# 1_FullBridge.net
KiCad netlist of a schematic drawn in Altium Designer
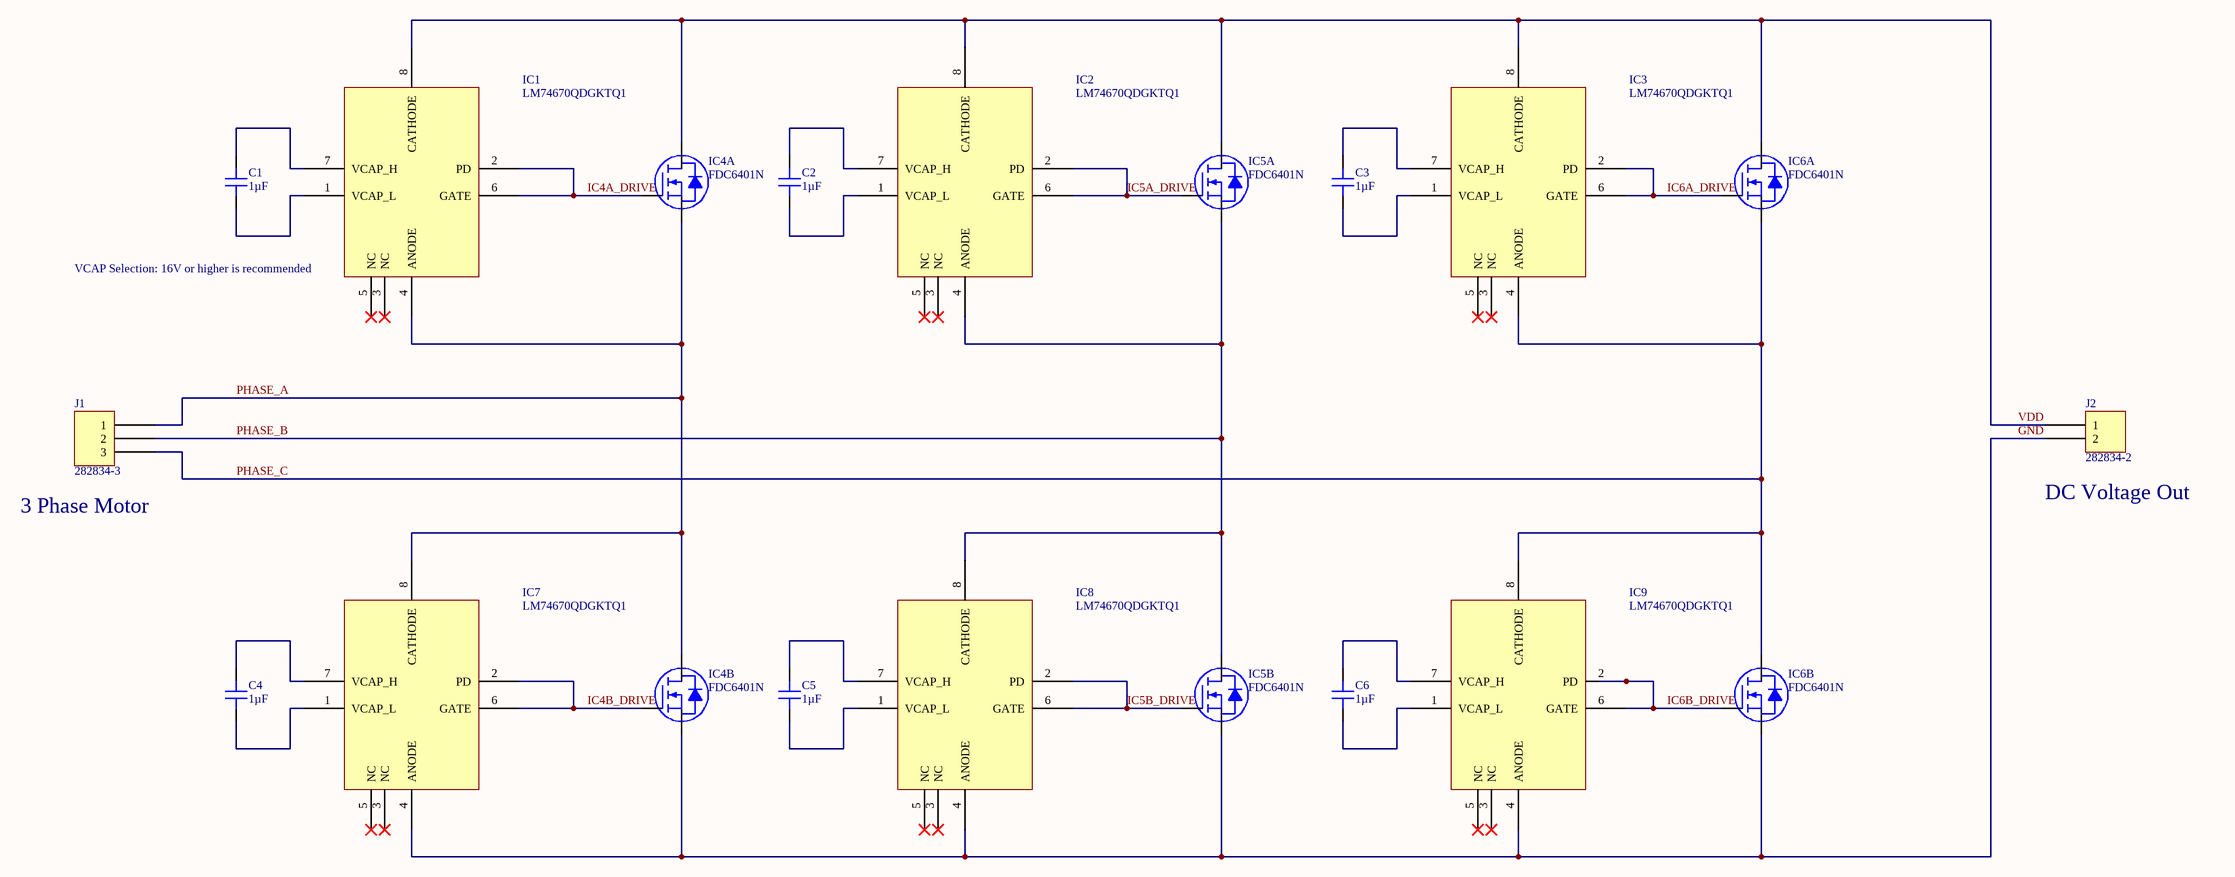
[diagram p0: 1_FullBridge.SchDoc]

(export (version "E")
  (design (tool "Eeschema 10.0.6"))
  (components
    (comp (ref "C1")
      (value "1µF")
      (footprint "CAP 0805_2012")
      (description "CAP CER 1UF 50V X7R 0805")
      (fields
        (field (name "PART NUMBER") "GCM21BR71H105KA03L")
        (field (name "MANUFACTURER") "Murata Electronics")
      )
      (libsource (lib "Celestial Altium Library - altium_library") (part "Capacitor"))
    )
    (comp (ref "C2")
      (value "1µF")
      (footprint "CAP 0805_2012")
      (description "CAP CER 1UF 50V X7R 0805")
      (fields
        (field (name "PART NUMBER") "GCM21BR71H105KA03L")
        (field (name "MANUFACTURER") "Murata Electronics")
      )
      (libsource (lib "Celestial Altium Library - altium_library") (part "Capacitor"))
    )
    (comp (ref "C3")
      (value "1µF")
      (footprint "CAP 0805_2012")
      (description "CAP CER 1UF 50V X7R 0805")
      (fields
        (field (name "PART NUMBER") "GCM21BR71H105KA03L")
        (field (name "MANUFACTURER") "Murata Electronics")
      )
      (libsource (lib "Celestial Altium Library - altium_library") (part "Capacitor"))
    )
    (comp (ref "C4")
      (value "1µF")
      (footprint "CAP 0805_2012")
      (description "CAP CER 1UF 50V X7R 0805")
      (fields
        (field (name "PART NUMBER") "GCM21BR71H105KA03L")
        (field (name "MANUFACTURER") "Murata Electronics")
      )
      (libsource (lib "Celestial Altium Library - altium_library") (part "Capacitor"))
    )
    (comp (ref "C5")
      (value "1µF")
      (footprint "CAP 0805_2012")
      (description "CAP CER 1UF 50V X7R 0805")
      (fields
        (field (name "PART NUMBER") "GCM21BR71H105KA03L")
        (field (name "MANUFACTURER") "Murata Electronics")
      )
      (libsource (lib "Celestial Altium Library - altium_library") (part "Capacitor"))
    )
    (comp (ref "C6")
      (value "1µF")
      (footprint "CAP 0805_2012")
      (description "CAP CER 1UF 50V X7R 0805")
      (fields
        (field (name "PART NUMBER") "GCM21BR71H105KA03L")
        (field (name "MANUFACTURER") "Murata Electronics")
      )
      (libsource (lib "Celestial Altium Library - altium_library") (part "Capacitor"))
    )
    (comp (ref "IC1")
      (value "LM74670QDGKTQ1")
      (footprint "TI_8VSSOP")
      (description "Zero IQ Smart Diode Rectifier Controller")
      (libsource (lib "bb_kinetic_harvester") (part "TI LM74670-Q1"))
    )
    (comp (ref "IC2")
      (value "LM74670QDGKTQ1")
      (footprint "TI_8VSSOP")
      (description "Zero IQ Smart Diode Rectifier Controller")
      (libsource (lib "bb_kinetic_harvester") (part "TI LM74670-Q1"))
    )
    (comp (ref "IC3")
      (value "LM74670QDGKTQ1")
      (footprint "TI_8VSSOP")
      (description "Zero IQ Smart Diode Rectifier Controller")
      (libsource (lib "bb_kinetic_harvester") (part "TI LM74670-Q1"))
    )
    (comp (ref "IC4")
      (value "FDC6401N")
      (footprint "FAIRCHILD SOT-23-6 SUPERSOT-6")
      (description "MOSFET 2N-CH 20V 3A SSOT-6")
      (fields (field (name "MANUFACTURER") "ON Semiconductor"))
      (libsource (lib "Celestial Altium Library - altium_library") (part "FAIRCHILD DUAL MOSFET N-CH SOT-23-6"))
    )
    (comp (ref "IC5")
      (value "FDC6401N")
      (footprint "FAIRCHILD SOT-23-6 SUPERSOT-6")
      (description "MOSFET 2N-CH 20V 3A SSOT-6")
      (fields (field (name "MANUFACTURER") "ON Semiconductor"))
      (libsource (lib "Celestial Altium Library - altium_library") (part "FAIRCHILD DUAL MOSFET N-CH SOT-23-6"))
    )
    (comp (ref "IC6")
      (value "FDC6401N")
      (footprint "FAIRCHILD SOT-23-6 SUPERSOT-6")
      (description "MOSFET 2N-CH 20V 3A SSOT-6")
      (fields (field (name "MANUFACTURER") "ON Semiconductor"))
      (libsource (lib "Celestial Altium Library - altium_library") (part "FAIRCHILD DUAL MOSFET N-CH SOT-23-6"))
    )
    (comp (ref "IC7")
      (value "LM74670QDGKTQ1")
      (footprint "TI_8VSSOP")
      (description "Zero IQ Smart Diode Rectifier Controller")
      (libsource (lib "bb_kinetic_harvester") (part "TI LM74670-Q1"))
    )
    (comp (ref "IC8")
      (value "LM74670QDGKTQ1")
      (footprint "TI_8VSSOP")
      (description "Zero IQ Smart Diode Rectifier Controller")
      (libsource (lib "bb_kinetic_harvester") (part "TI LM74670-Q1"))
    )
    (comp (ref "IC9")
      (value "LM74670QDGKTQ1")
      (footprint "TI_8VSSOP")
      (description "Zero IQ Smart Diode Rectifier Controller")
      (libsource (lib "bb_kinetic_harvester") (part "TI LM74670-Q1"))
    )
    (comp (ref "J1")
      (value "282834-3")
      (footprint "TE 282834-3")
      (description "TERM BLK 3P SIDE ENT 2.54MM PCB")
      (fields (field (name "MANUFACTURER") "TE Connectivity AMP Connectors") (field (name "VOLTAGE") "150V"))
      (libsource (lib "Celestial Altium Library - altium_library") (part "3 Pin"))
    )
    (comp (ref "J2")
      (value "282834-2")
      (footprint "TE 282834-2")
      (description "TERM BLK 2P SIDE ENT 2.54MM PCB")
      (fields (field (name "MANUFACTURER") "TE Connectivity AMP Connectors") (field (name "VOLTAGE") "150V"))
      (libsource (lib "Celestial Altium Library - altium_library") (part "2 Pin"))
    )
  )
  (nets
    (net (code "1") (name "/GND") (class "Default")
      (node (ref "IC4") (pin "2") (pinfunction "S2_2") (pintype "passive"))
      (node (ref "IC5") (pin "2") (pinfunction "S2_2") (pintype "passive"))
      (node (ref "IC6") (pin "2") (pinfunction "S2_2") (pintype "passive"))
      (node (ref "IC7") (pin "4") (pinfunction "ANODE_4") (pintype "passive"))
      (node (ref "IC8") (pin "4") (pinfunction "ANODE_4") (pintype "passive"))
      (node (ref "IC9") (pin "4") (pinfunction "ANODE_4") (pintype "passive"))
      (node (ref "J2") (pin "2") (pinfunction "2_2") (pintype "passive"))
    )
    (net (code "2") (name "/IC4A_DRIVE") (class "Default")
      (node (ref "IC1") (pin "2") (pinfunction "PD_2") (pintype "passive"))
      (node (ref "IC1") (pin "6") (pinfunction "GATE_6") (pintype "passive"))
      (node (ref "IC4") (pin "1") (pinfunction "G1_1") (pintype "passive"))
    )
    (net (code "3") (name "/IC4B_DRIVE") (class "Default")
      (node (ref "IC4") (pin "3") (pinfunction "G2_3") (pintype "passive"))
      (node (ref "IC7") (pin "2") (pinfunction "PD_2") (pintype "passive"))
      (node (ref "IC7") (pin "6") (pinfunction "GATE_6") (pintype "passive"))
    )
    (net (code "4") (name "/IC5A_DRIVE") (class "Default")
      (node (ref "IC2") (pin "2") (pinfunction "PD_2") (pintype "passive"))
      (node (ref "IC2") (pin "6") (pinfunction "GATE_6") (pintype "passive"))
      (node (ref "IC5") (pin "1") (pinfunction "G1_1") (pintype "passive"))
    )
    (net (code "5") (name "/IC5B_DRIVE") (class "Default")
      (node (ref "IC5") (pin "3") (pinfunction "G2_3") (pintype "passive"))
      (node (ref "IC8") (pin "2") (pinfunction "PD_2") (pintype "passive"))
      (node (ref "IC8") (pin "6") (pinfunction "GATE_6") (pintype "passive"))
    )
    (net (code "6") (name "/IC6A_DRIVE") (class "Default")
      (node (ref "IC3") (pin "2") (pinfunction "PD_2") (pintype "passive"))
      (node (ref "IC3") (pin "6") (pinfunction "GATE_6") (pintype "passive"))
      (node (ref "IC6") (pin "1") (pinfunction "G1_1") (pintype "passive"))
    )
    (net (code "7") (name "/IC6B_DRIVE") (class "Default")
      (node (ref "IC6") (pin "3") (pinfunction "G2_3") (pintype "passive"))
      (node (ref "IC9") (pin "2") (pinfunction "PD_2") (pintype "passive"))
      (node (ref "IC9") (pin "6") (pinfunction "GATE_6") (pintype "passive"))
    )
    (net (code "8") (name "/PHASE_A") (class "Default")
      (node (ref "IC1") (pin "4") (pinfunction "ANODE_4") (pintype "passive"))
      (node (ref "IC4") (pin "4") (pinfunction "D2_4") (pintype "passive"))
      (node (ref "IC4") (pin "5") (pinfunction "S1_5") (pintype "passive"))
      (node (ref "IC7") (pin "8") (pinfunction "CATHODE_8") (pintype "passive"))
      (node (ref "J1") (pin "1") (pinfunction "1_1") (pintype "passive"))
    )
    (net (code "9") (name "/PHASE_B") (class "Default")
      (node (ref "IC2") (pin "4") (pinfunction "ANODE_4") (pintype "passive"))
      (node (ref "IC5") (pin "4") (pinfunction "D2_4") (pintype "passive"))
      (node (ref "IC5") (pin "5") (pinfunction "S1_5") (pintype "passive"))
      (node (ref "IC8") (pin "8") (pinfunction "CATHODE_8") (pintype "passive"))
      (node (ref "J1") (pin "2") (pinfunction "2_2") (pintype "passive"))
    )
    (net (code "10") (name "/PHASE_C") (class "Default")
      (node (ref "IC3") (pin "4") (pinfunction "ANODE_4") (pintype "passive"))
      (node (ref "IC6") (pin "4") (pinfunction "D2_4") (pintype "passive"))
      (node (ref "IC6") (pin "5") (pinfunction "S1_5") (pintype "passive"))
      (node (ref "IC9") (pin "8") (pinfunction "CATHODE_8") (pintype "passive"))
      (node (ref "J1") (pin "3") (pinfunction "3_3") (pintype "passive"))
    )
    (net (code "11") (name "/VDD") (class "Default")
      (node (ref "IC1") (pin "8") (pinfunction "CATHODE_8") (pintype "passive"))
      (node (ref "IC2") (pin "8") (pinfunction "CATHODE_8") (pintype "passive"))
      (node (ref "IC3") (pin "8") (pinfunction "CATHODE_8") (pintype "passive"))
      (node (ref "IC4") (pin "6") (pinfunction "D1_6") (pintype "passive"))
      (node (ref "IC5") (pin "6") (pinfunction "D1_6") (pintype "passive"))
      (node (ref "IC6") (pin "6") (pinfunction "D1_6") (pintype "passive"))
      (node (ref "J2") (pin "1") (pinfunction "1_1") (pintype "passive"))
    )
    (net (code "12") (name "Net-(IC1-VCAP_H)") (class "Default")
      (node (ref "C1") (pin "1") (pinfunction "1_1") (pintype "passive"))
      (node (ref "IC1") (pin "7") (pinfunction "VCAP_H_7") (pintype "passive"))
    )
    (net (code "13") (name "Net-(IC1-VCAP_L)") (class "Default")
      (node (ref "C1") (pin "2") (pinfunction "2_2") (pintype "passive"))
      (node (ref "IC1") (pin "1") (pinfunction "VCAP_L_1") (pintype "passive"))
    )
    (net (code "14") (name "Net-(IC2-VCAP_H)") (class "Default")
      (node (ref "C2") (pin "1") (pinfunction "1_1") (pintype "passive"))
      (node (ref "IC2") (pin "7") (pinfunction "VCAP_H_7") (pintype "passive"))
    )
    (net (code "15") (name "Net-(IC2-VCAP_L)") (class "Default")
      (node (ref "C2") (pin "2") (pinfunction "2_2") (pintype "passive"))
      (node (ref "IC2") (pin "1") (pinfunction "VCAP_L_1") (pintype "passive"))
    )
    (net (code "16") (name "Net-(IC3-VCAP_H)") (class "Default")
      (node (ref "C3") (pin "1") (pinfunction "1_1") (pintype "passive"))
      (node (ref "IC3") (pin "7") (pinfunction "VCAP_H_7") (pintype "passive"))
    )
    (net (code "17") (name "Net-(IC3-VCAP_L)") (class "Default")
      (node (ref "C3") (pin "2") (pinfunction "2_2") (pintype "passive"))
      (node (ref "IC3") (pin "1") (pinfunction "VCAP_L_1") (pintype "passive"))
    )
    (net (code "18") (name "Net-(IC7-VCAP_H)") (class "Default")
      (node (ref "C4") (pin "1") (pinfunction "1_1") (pintype "passive"))
      (node (ref "IC7") (pin "7") (pinfunction "VCAP_H_7") (pintype "passive"))
    )
    (net (code "19") (name "Net-(IC7-VCAP_L)") (class "Default")
      (node (ref "C4") (pin "2") (pinfunction "2_2") (pintype "passive"))
      (node (ref "IC7") (pin "1") (pinfunction "VCAP_L_1") (pintype "passive"))
    )
    (net (code "20") (name "Net-(IC8-VCAP_H)") (class "Default")
      (node (ref "C5") (pin "1") (pinfunction "1_1") (pintype "passive"))
      (node (ref "IC8") (pin "7") (pinfunction "VCAP_H_7") (pintype "passive"))
    )
    (net (code "21") (name "Net-(IC8-VCAP_L)") (class "Default")
      (node (ref "C5") (pin "2") (pinfunction "2_2") (pintype "passive"))
      (node (ref "IC8") (pin "1") (pinfunction "VCAP_L_1") (pintype "passive"))
    )
    (net (code "22") (name "Net-(IC9-VCAP_H)") (class "Default")
      (node (ref "C6") (pin "1") (pinfunction "1_1") (pintype "passive"))
      (node (ref "IC9") (pin "7") (pinfunction "VCAP_H_7") (pintype "passive"))
    )
    (net (code "23") (name "Net-(IC9-VCAP_L)") (class "Default")
      (node (ref "C6") (pin "2") (pinfunction "2_2") (pintype "passive"))
      (node (ref "IC9") (pin "1") (pinfunction "VCAP_L_1") (pintype "passive"))
    )
    (net (code "24") (name "unconnected-(IC1-NC-Pad3)") (class "Default")
      (node (ref "IC1") (pin "3") (pinfunction "NC_3") (pintype "passive+no_connect"))
    )
    (net (code "25") (name "unconnected-(IC1-NC-Pad5)") (class "Default")
      (node (ref "IC1") (pin "5") (pinfunction "NC_5") (pintype "passive+no_connect"))
    )
    (net (code "26") (name "unconnected-(IC2-NC-Pad3)") (class "Default")
      (node (ref "IC2") (pin "3") (pinfunction "NC_3") (pintype "passive+no_connect"))
    )
    (net (code "27") (name "unconnected-(IC2-NC-Pad5)") (class "Default")
      (node (ref "IC2") (pin "5") (pinfunction "NC_5") (pintype "passive+no_connect"))
    )
    (net (code "28") (name "unconnected-(IC3-NC-Pad3)") (class "Default")
      (node (ref "IC3") (pin "3") (pinfunction "NC_3") (pintype "passive+no_connect"))
    )
    (net (code "29") (name "unconnected-(IC3-NC-Pad5)") (class "Default")
      (node (ref "IC3") (pin "5") (pinfunction "NC_5") (pintype "passive+no_connect"))
    )
    (net (code "30") (name "unconnected-(IC7-NC-Pad3)") (class "Default")
      (node (ref "IC7") (pin "3") (pinfunction "NC_3") (pintype "passive+no_connect"))
    )
    (net (code "31") (name "unconnected-(IC7-NC-Pad5)") (class "Default")
      (node (ref "IC7") (pin "5") (pinfunction "NC_5") (pintype "passive+no_connect"))
    )
    (net (code "32") (name "unconnected-(IC8-NC-Pad3)") (class "Default")
      (node (ref "IC8") (pin "3") (pinfunction "NC_3") (pintype "passive+no_connect"))
    )
    (net (code "33") (name "unconnected-(IC8-NC-Pad5)") (class "Default")
      (node (ref "IC8") (pin "5") (pinfunction "NC_5") (pintype "passive+no_connect"))
    )
    (net (code "34") (name "unconnected-(IC9-NC-Pad3)") (class "Default")
      (node (ref "IC9") (pin "3") (pinfunction "NC_3") (pintype "passive+no_connect"))
    )
    (net (code "35") (name "unconnected-(IC9-NC-Pad5)") (class "Default")
      (node (ref "IC9") (pin "5") (pinfunction "NC_5") (pintype "passive+no_connect"))
    )
  )
)
